# power.net
KiCad netlist of a schematic drawn in Altium Designer
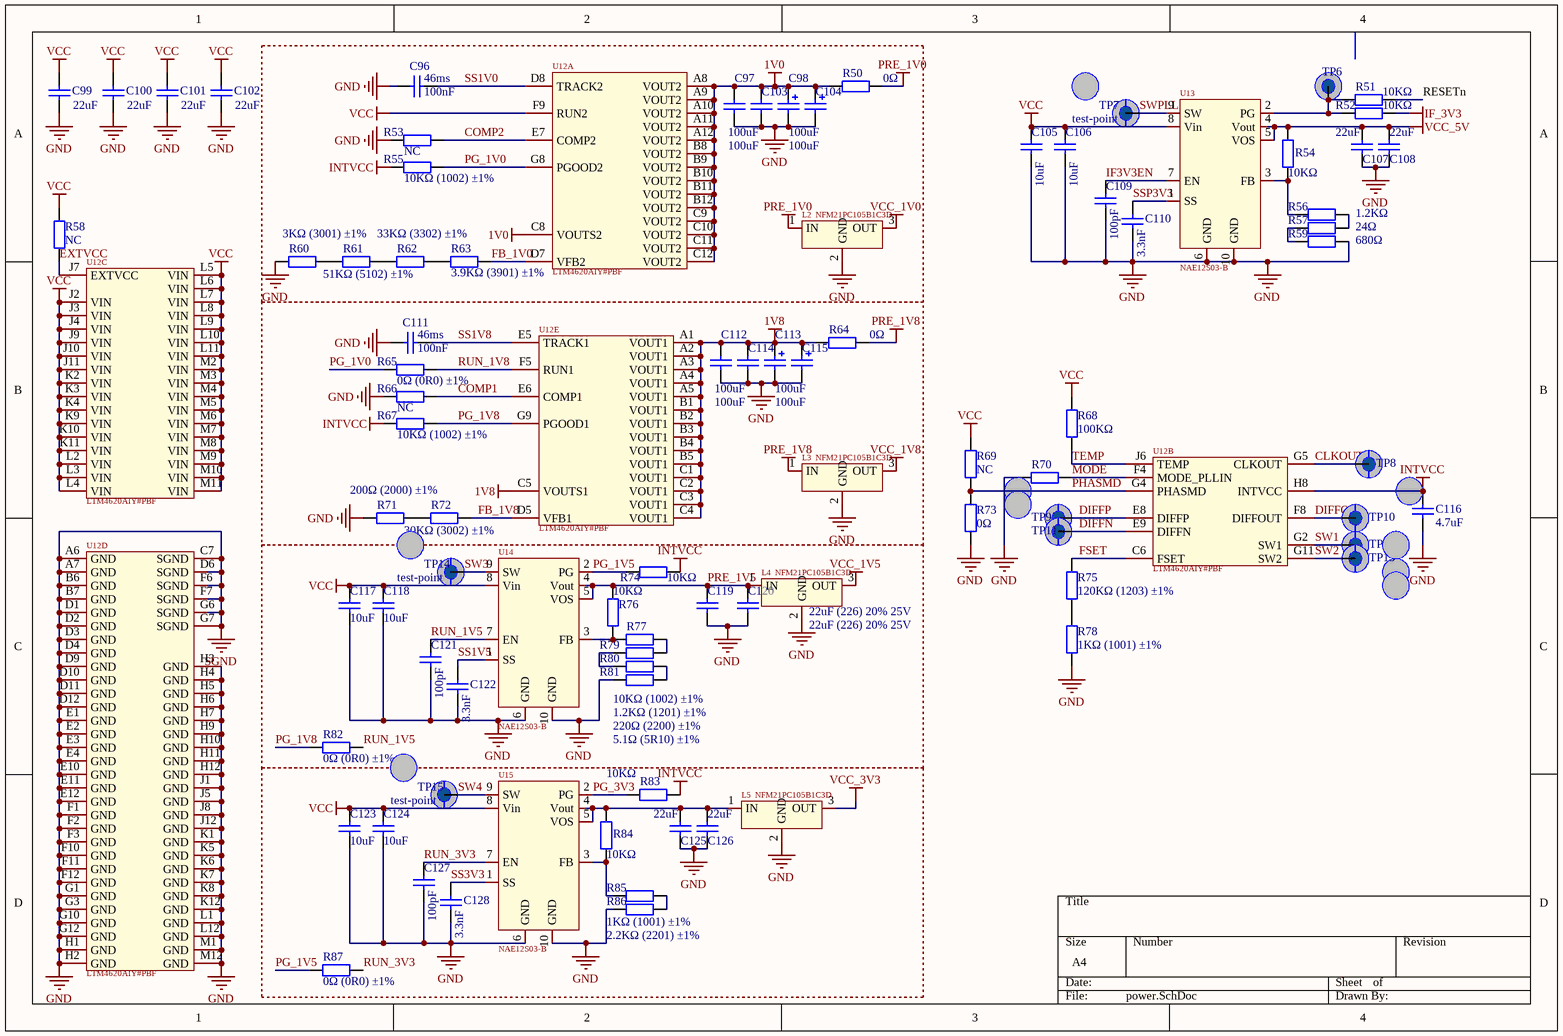
[diagram p0: power.SchDoc]

(export (version "E")
  (design (tool "Eeschema 10.0.6"))
  (components
    (comp (ref "C96")
      (value "100nF")
      (footprint "0805_C")
      (description "贴片电容")
      (libsource (lib "Miscellaneous Devices LC") (part "0805 100nF(104) 10% 50V"))
    )
    (comp (ref "C97")
      (value "100uF")
      (footprint "1206_C")
      (description "贴片电容")
      (libsource (lib "Miscellaneous Devices LC") (part "1206 100nF (104) 10% 50V"))
    )
    (comp (ref "C98")
      (value "100uF")
      (footprint "CASE-B_3528")
      (description "钽电容")
      (libsource (lib "Miscellaneous Devices LC") (part "3528 100uF (107) 10% 6.3V"))
    )
    (comp (ref "C99")
      (value "22uF")
      (footprint "0805_C")
      (description "贴片电容")
      (libsource (lib "Miscellaneous Devices LC") (part "0805 22uF (226) 20% 25V"))
    )
    (comp (ref "C100")
      (value "22uF")
      (footprint "0805_C")
      (description "贴片电容")
      (libsource (lib "Miscellaneous Devices LC") (part "0805 22uF (226) 20% 25V"))
    )
    (comp (ref "C101")
      (value "22uF")
      (footprint "0805_C")
      (description "贴片电容")
      (libsource (lib "Miscellaneous Devices LC") (part "0805 22uF (226) 20% 25V"))
    )
    (comp (ref "C102")
      (value "22uF")
      (footprint "0805_C")
      (description "贴片电容")
      (libsource (lib "Miscellaneous Devices LC") (part "0805 22uF (226) 20% 25V"))
    )
    (comp (ref "C103")
      (value "100uF")
      (footprint "1206_C")
      (description "贴片电容")
      (libsource (lib "Miscellaneous Devices LC") (part "1206 100nF (104) 10% 50V"))
    )
    (comp (ref "C104")
      (value "100uF")
      (footprint "CASE-B_3528")
      (description "钽电容")
      (libsource (lib "Miscellaneous Devices LC") (part "3528 100uF (107) 10% 6.3V"))
    )
    (comp (ref "C105")
      (value "10uF")
      (footprint "0805_C")
      (description "贴片电容")
      (libsource (lib "Miscellaneous Devices LC") (part "0805 10uF (106) 10% 25V"))
    )
    (comp (ref "C106")
      (value "10uF")
      (footprint "0805_C")
      (description "贴片电容")
      (libsource (lib "Miscellaneous Devices LC") (part "0805 10uF (106) 10% 25V"))
    )
    (comp (ref "C107")
      (value "22uF")
      (footprint "0805_C")
      (description "贴片电容")
      (libsource (lib "Miscellaneous Devices LC") (part "0805 22uF (226) 20% 25V"))
    )
    (comp (ref "C108")
      (value "22uF")
      (footprint "0805_C")
      (description "贴片电容")
      (libsource (lib "Miscellaneous Devices LC") (part "0805 22uF (226) 20% 25V"))
    )
    (comp (ref "C109")
      (value "100pF")
      (footprint "0805_C")
      (description "贴片电容")
      (libsource (lib "Miscellaneous Devices LC") (part "0805 100pF (101) 5% 50V"))
    )
    (comp (ref "C110")
      (value "3.3nF")
      (footprint "0805_C")
      (description "贴片电容")
      (libsource (lib "Miscellaneous Devices LC") (part "0805 3.3nF (332) 10% 50V"))
    )
    (comp (ref "C111")
      (value "100nF")
      (footprint "0805_C")
      (description "贴片电容")
      (libsource (lib "Miscellaneous Devices LC") (part "0805 100nF(104) 10% 50V"))
    )
    (comp (ref "C112")
      (value "100uF")
      (footprint "1206_C")
      (description "贴片电容")
      (libsource (lib "Miscellaneous Devices LC") (part "1206 100nF (104) 10% 50V"))
    )
    (comp (ref "C113")
      (value "100uF")
      (footprint "CASE-B_3528")
      (description "钽电容")
      (libsource (lib "Miscellaneous Devices LC") (part "3528 100uF (107) 10% 6.3V"))
    )
    (comp (ref "C114")
      (value "100uF")
      (footprint "1206_C")
      (description "贴片电容")
      (libsource (lib "Miscellaneous Devices LC") (part "1206 100nF (104) 10% 50V"))
    )
    (comp (ref "C115")
      (value "100uF")
      (footprint "CASE-B_3528")
      (description "钽电容")
      (libsource (lib "Miscellaneous Devices LC") (part "3528 100uF (107) 10% 6.3V"))
    )
    (comp (ref "C116")
      (value "4.7uF")
      (footprint "0805_C")
      (description "贴片电容")
      (libsource (lib "Miscellaneous Devices LC") (part "0805 4.7uF (475) 10% 25V"))
    )
    (comp (ref "C117")
      (value "10uF")
      (footprint "0805_C")
      (description "贴片电容")
      (libsource (lib "Miscellaneous Devices LC") (part "0805 10uF (106) 10% 25V"))
    )
    (comp (ref "C118")
      (value "10uF")
      (footprint "0805_C")
      (description "贴片电容")
      (libsource (lib "Miscellaneous Devices LC") (part "0805 10uF (106) 10% 25V"))
    )
    (comp (ref "C119")
      (value "22uF (226) 20% 25V")
      (footprint "0805_C")
      (description "贴片电容")
      (libsource (lib "Miscellaneous Devices LC") (part "0805 22uF (226) 20% 25V"))
    )
    (comp (ref "C120")
      (value "22uF (226) 20% 25V")
      (footprint "0805_C")
      (description "贴片电容")
      (libsource (lib "Miscellaneous Devices LC") (part "0805 22uF (226) 20% 25V"))
    )
    (comp (ref "C121")
      (value "100pF")
      (footprint "0805_C")
      (description "贴片电容")
      (libsource (lib "Miscellaneous Devices LC") (part "0805 100pF (101) 5% 50V"))
    )
    (comp (ref "C122")
      (value "3.3nF")
      (footprint "0805_C")
      (description "贴片电容")
      (libsource (lib "Miscellaneous Devices LC") (part "0805 3.3nF (332) 10% 50V"))
    )
    (comp (ref "C123")
      (value "10uF")
      (footprint "0805_C")
      (description "贴片电容")
      (libsource (lib "Miscellaneous Devices LC") (part "0805 10uF (106) 10% 25V"))
    )
    (comp (ref "C124")
      (value "10uF")
      (footprint "0805_C")
      (description "贴片电容")
      (libsource (lib "Miscellaneous Devices LC") (part "0805 10uF (106) 10% 25V"))
    )
    (comp (ref "C125")
      (value "22uF")
      (footprint "0805_C")
      (description "贴片电容")
      (libsource (lib "Miscellaneous Devices LC") (part "0805 22uF (226) 20% 25V"))
    )
    (comp (ref "C126")
      (value "22uF")
      (footprint "0805_C")
      (description "贴片电容")
      (libsource (lib "Miscellaneous Devices LC") (part "0805 22uF (226) 20% 25V"))
    )
    (comp (ref "C127")
      (value "100pF")
      (footprint "0805_C")
      (description "贴片电容")
      (libsource (lib "Miscellaneous Devices LC") (part "0805 100pF (101) 5% 50V"))
    )
    (comp (ref "C128")
      (value "3.3nF")
      (footprint "0805_C")
      (description "贴片电容")
      (libsource (lib "Miscellaneous Devices LC") (part "0805 3.3nF (332) 10% 50V"))
    )
    (comp (ref "L2")
      (value "NFM21PC105B1C3D")
      (footprint "FILTER-SMD_3P-L2.0-W1.2-L")
      (description "穿心电容")
      (fields (field (name "MANUFACTURER") "muRata(村田)"))
      (libsource (lib "五向开关") (part "NFM21PC105B1C3D"))
    )
    (comp (ref "L3")
      (value "NFM21PC105B1C3D")
      (footprint "FILTER-SMD_3P-L2.0-W1.2-L")
      (description "穿心电容")
      (fields (field (name "MANUFACTURER") "muRata(村田)"))
      (libsource (lib "五向开关") (part "NFM21PC105B1C3D"))
    )
    (comp (ref "L4")
      (value "NFM21PC105B1C3D")
      (footprint "FILTER-SMD_3P-L2.0-W1.2-L")
      (description "穿心电容")
      (fields (field (name "MANUFACTURER") "muRata(村田)"))
      (libsource (lib "五向开关") (part "NFM21PC105B1C3D"))
    )
    (comp (ref "L5")
      (value "NFM21PC105B1C3D")
      (footprint "FILTER-SMD_3P-L2.0-W1.2-L")
      (description "穿心电容")
      (fields (field (name "MANUFACTURER") "muRata(村田)"))
      (libsource (lib "五向开关") (part "NFM21PC105B1C3D"))
    )
    (comp (ref "R50")
      (value "0Ω")
      (footprint "0402_R")
      (description "贴片电阻")
      (libsource (lib "") (part "0805 0Ω (0R0) 1%_1"))
    )
    (comp (ref "R51")
      (value "10KΩ")
      (footprint "0805_R")
      (description "贴片电阻")
      (libsource (lib "Miscellaneous Devices LC") (part "0805 10KΩ (1002) 1%"))
    )
    (comp (ref "R52")
      (value "10KΩ")
      (footprint "0805_R")
      (description "贴片电阻")
      (libsource (lib "Miscellaneous Devices LC") (part "0805 10KΩ (1002) 1%"))
    )
    (comp (ref "R53")
      (value "NC")
      (footprint "0805_R")
      (description "贴片电阻")
      (libsource (lib "Miscellaneous Devices LC") (part "0805 33KΩ (3302) 1%"))
    )
    (comp (ref "R54")
      (value "10KΩ")
      (footprint "0805_R")
      (description "贴片电阻")
      (libsource (lib "") (part "0805 10KΩ (1002) 1%_1"))
    )
    (comp (ref "R55")
      (value "10KΩ (1002) ±1%")
      (footprint "0805_R")
      (description "贴片电阻")
      (libsource (lib "Miscellaneous Devices LC") (part "0805 10KΩ (1002) 1%"))
    )
    (comp (ref "R56")
      (value "1.2KΩ")
      (footprint "0805_R")
      (description "贴片电阻")
      (libsource (lib "Miscellaneous Devices LC") (part "0805 2.2KΩ (2201) 1%"))
    )
    (comp (ref "R57")
      (value "24Ω")
      (footprint "0805_R")
      (description "贴片电阻")
      (libsource (lib "") (part "0805 1KΩ (1001) 1%_1"))
    )
    (comp (ref "R58")
      (value "NC")
      (footprint "0805_R")
      (description "贴片电阻")
      (libsource (lib "") (part "0805 3KΩ (3001) 1%_1"))
    )
    (comp (ref "R59")
      (value "680Ω")
      (footprint "0805_R")
      (description "贴片电阻")
      (libsource (lib "") (part "0805 1KΩ (1001) 1%_1"))
    )
    (comp (ref "R60")
      (value "3KΩ (3001) ±1%")
      (footprint "0805_R")
      (description "贴片电阻")
      (libsource (lib "Miscellaneous Devices LC") (part "0805 3KΩ (3001) 1%"))
    )
    (comp (ref "R61")
      (value "51KΩ (5102) ±1%")
      (footprint "0805_R")
      (description "贴片电阻")
      (libsource (lib "Miscellaneous Devices LC") (part "0805 51KΩ (5102) 1%"))
    )
    (comp (ref "R62")
      (value "33KΩ (3302) ±1%")
      (footprint "0805_R")
      (description "贴片电阻")
      (libsource (lib "Miscellaneous Devices LC") (part "0805 33KΩ (3302) 1%"))
    )
    (comp (ref "R63")
      (value "3.9KΩ (3901) ±1%")
      (footprint "0805_R")
      (description "贴片电阻")
      (libsource (lib "Miscellaneous Devices LC") (part "0805 3.9KΩ (3901) 1%"))
    )
    (comp (ref "R64")
      (value "0Ω")
      (footprint "0402_R")
      (description "贴片电阻")
      (libsource (lib "") (part "0805 0Ω (0R0) 1%_1"))
    )
    (comp (ref "R65")
      (value "0Ω (0R0) ±1%")
      (footprint "0805_R")
      (description "贴片电阻")
      (libsource (lib "Miscellaneous Devices LC") (part "0805 0Ω (0R0) 1%"))
    )
    (comp (ref "R66")
      (value "NC")
      (footprint "0805_R")
      (description "贴片电阻")
      (libsource (lib "Miscellaneous Devices LC") (part "0805 33KΩ (3302) 1%"))
    )
    (comp (ref "R67")
      (value "10KΩ (1002) ±1%")
      (footprint "0805_R")
      (description "贴片电阻")
      (libsource (lib "Miscellaneous Devices LC") (part "0805 10KΩ (1002) 1%"))
    )
    (comp (ref "R68")
      (value "100KΩ")
      (footprint "0805_R")
      (description "贴片电阻")
      (libsource (lib "Miscellaneous Devices LC") (part "0805 100KΩ (1003) 1%"))
    )
    (comp (ref "R69")
      (value "NC")
      (footprint "0805_R")
      (description "贴片电阻")
      (libsource (lib "") (part "0805 0Ω (0R0) 1%_2"))
    )
    (comp (ref "R70")
      (value "0Ω")
      (footprint "0805_R")
      (description "贴片电阻")
      (libsource (lib "Miscellaneous Devices LC") (part "0805 0Ω (0R0) 1%"))
    )
    (comp (ref "R71")
      (value "200Ω (2000) ±1%")
      (footprint "0805_R")
      (description "贴片电阻")
      (libsource (lib "Miscellaneous Devices LC") (part "0805 200Ω (2000) 1%"))
    )
    (comp (ref "R72")
      (value "30KΩ (3002) ±1%")
      (footprint "0805_R")
      (description "贴片电阻")
      (libsource (lib "Miscellaneous Devices LC") (part "0805 33KΩ (3302) 1%"))
    )
    (comp (ref "R73")
      (value "0Ω")
      (footprint "0805_R")
      (description "贴片电阻")
      (libsource (lib "") (part "0805 0Ω (0R0) 1%_2"))
    )
    (comp (ref "R74")
      (value "10KΩ")
      (footprint "0805_R")
      (description "贴片电阻")
      (libsource (lib "") (part "0805 10KΩ (1002) 1%_2"))
    )
    (comp (ref "R75")
      (value "120KΩ (1203) ±1%")
      (footprint "0805_R")
      (description "贴片电阻")
      (libsource (lib "Miscellaneous Devices LC") (part "0402 120KΩ (1203) 1%"))
    )
    (comp (ref "R76")
      (value "10KΩ")
      (footprint "0805_R")
      (description "贴片电阻")
      (libsource (lib "") (part "0805 10KΩ (1002) 1%_1"))
    )
    (comp (ref "R77")
      (value "10KΩ (1002) ±1%")
      (footprint "0805_R")
      (description "贴片电阻")
      (libsource (lib "") (part "0805 10KΩ (1002) 1%_2"))
    )
    (comp (ref "R78")
      (value "1KΩ (1001) ±1%")
      (footprint "0805_R")
      (description "贴片电阻")
      (libsource (lib "Miscellaneous Devices LC") (part "0402 1KΩ (1001) 1%"))
    )
    (comp (ref "R79")
      (value "1.2KΩ (1201) ±1%")
      (footprint "0805_R")
      (description "贴片电阻")
      (libsource (lib "Miscellaneous Devices LC") (part "0805 1.2KΩ (1201) 1%"))
    )
    (comp (ref "R80")
      (value "220Ω (2200) ±1%")
      (footprint "0805_R")
      (description "贴片电阻")
      (libsource (lib "Miscellaneous Devices LC") (part "0805 220Ω (2200) 1%"))
    )
    (comp (ref "R81")
      (value "5.1Ω (5R10) ±1%")
      (footprint "0805_R")
      (description "贴片电阻")
      (libsource (lib "Miscellaneous Devices LC") (part "0805 5.1Ω (5R10) 1%"))
    )
    (comp (ref "R82")
      (value "0Ω (0R0) ±1%")
      (footprint "0805_R")
      (description "贴片电阻")
      (libsource (lib "Miscellaneous Devices LC") (part "0805 0Ω (0R0) 1%"))
    )
    (comp (ref "R83")
      (value "10KΩ")
      (footprint "0805_R")
      (description "贴片电阻")
      (libsource (lib "") (part "0805 10KΩ (1002) 1%_2"))
    )
    (comp (ref "R84")
      (value "10KΩ")
      (footprint "0805_R")
      (description "贴片电阻")
      (libsource (lib "") (part "0805 10KΩ (1002) 1%_1"))
    )
    (comp (ref "R85")
      (value "2.2KΩ (2201) ±1%")
      (footprint "0805_R")
      (description "贴片电阻")
      (libsource (lib "Miscellaneous Devices LC") (part "0805 2.2KΩ (2201) 1%"))
    )
    (comp (ref "R86")
      (value "1KΩ (1001) ±1%")
      (footprint "0805_R")
      (description "贴片电阻")
      (libsource (lib "Miscellaneous Devices LC") (part "0805 1KΩ (1001) 1%"))
    )
    (comp (ref "R87")
      (value "0Ω (0R0) ±1%")
      (footprint "0805_R")
      (description "贴片电阻")
      (libsource (lib "Miscellaneous Devices LC") (part "0805 0Ω (0R0) 1%"))
    )
    (comp (ref "TP6")
      (value "test-point")
      (footprint "POINT")
      (description "测试点")
      (libsource (lib "") (part "test-point_2"))
    )
    (comp (ref "TP7")
      (value "test-point")
      (footprint "POINT")
      (description "测试点")
      (libsource (lib "五向开关") (part "test-point"))
    )
    (comp (ref "TP8")
      (value "test-point")
      (footprint "POINT")
      (description "测试点")
      (libsource (lib "") (part "test-point_1"))
    )
    (comp (ref "TP9")
      (value "test-point")
      (footprint "POINT")
      (description "测试点")
      (libsource (lib "五向开关") (part "test-point"))
    )
    (comp (ref "TP10")
      (value "test-point")
      (footprint "POINT")
      (description "测试点")
      (libsource (lib "") (part "test-point_1"))
    )
    (comp (ref "TP11")
      (value "test-point")
      (footprint "POINT")
      (description "测试点")
      (libsource (lib "五向开关") (part "test-point"))
    )
    (comp (ref "TP12")
      (value "test-point")
      (footprint "POINT")
      (description "测试点")
      (libsource (lib "") (part "test-point_1"))
    )
    (comp (ref "TP13")
      (value "test-point")
      (footprint "POINT")
      (description "测试点")
      (libsource (lib "") (part "test-point_1"))
    )
    (comp (ref "TP14")
      (value "test-point")
      (footprint "POINT")
      (description "测试点")
      (libsource (lib "五向开关") (part "test-point"))
    )
    (comp (ref "TP15")
      (value "test-point")
      (footprint "POINT")
      (description "测试点")
      (libsource (lib "五向开关") (part "test-point"))
    )
    (comp (ref "U12")
      (value "LTM4620AIY#PBF")
      (footprint "BGA-144_L15.0-W15.0-R12-C12-P1.27-BL")
      (description "ADI电源")
      (fields (field (name "MANUFACTURER") "ADI(亚德诺)"))
      (libsource (lib "五向开关") (part "LTM4620AIY#PBF"))
    )
    (comp (ref "U13")
      (value "NAE12S03-B")
      (footprint "PWRM-SMD_HUAWEI_NAE12S03")
      (description "华为电源模块")
      (fields (field (name "MANUFACTURER") "HUAWEI(华为)"))
      (libsource (lib "五向开关") (part "NAE12S03-B"))
    )
    (comp (ref "U14")
      (value "NAE12S03-B")
      (footprint "PWRM-SMD_HUAWEI_NAE12S03")
      (description "华为电源模块")
      (fields (field (name "MANUFACTURER") "HUAWEI(华为)"))
      (libsource (lib "五向开关") (part "NAE12S03-B"))
    )
    (comp (ref "U15")
      (value "NAE12S03-B")
      (footprint "PWRM-SMD_HUAWEI_NAE12S03")
      (description "华为电源模块")
      (fields (field (name "MANUFACTURER") "HUAWEI(华为)"))
      (libsource (lib "五向开关") (part "NAE12S03-B"))
    )
  )
  (nets
    (net (code "1") (name "/CLKOUT") (class "Default")
      (node (ref "TP8") (pin "1") (pinfunction "point_1") (pintype "passive"))
      (node (ref "U12") (pin "G5") (pinfunction "CLKOUT_G5") (pintype "passive"))
    )
    (net (code "2") (name "/COMP1") (class "Default")
      (node (ref "R66") (pin "2") (pinfunction "2_2") (pintype "passive"))
      (node (ref "U12") (pin "E6") (pinfunction "COMP1_E6") (pintype "passive"))
    )
    (net (code "3") (name "/COMP2") (class "Default")
      (node (ref "R53") (pin "2") (pinfunction "2_2") (pintype "passive"))
      (node (ref "U12") (pin "E7") (pinfunction "COMP2_E7") (pintype "passive"))
    )
    (net (code "4") (name "/DIFFN") (class "Default")
      (node (ref "TP11") (pin "1") (pinfunction "point_1") (pintype "passive"))
      (node (ref "U12") (pin "E9") (pinfunction "DIFFN_E9") (pintype "passive"))
    )
    (net (code "5") (name "/DIFFO") (class "Default")
      (node (ref "TP10") (pin "1") (pinfunction "point_1") (pintype "passive"))
      (node (ref "U12") (pin "F8") (pinfunction "DIFFOUT_F8") (pintype "passive"))
    )
    (net (code "6") (name "/DIFFP") (class "Default")
      (node (ref "TP9") (pin "1") (pinfunction "point_1") (pintype "passive"))
      (node (ref "U12") (pin "E8") (pinfunction "DIFFP_E8") (pintype "passive"))
    )
    (net (code "7") (name "/EXTVCC") (class "Default")
      (node (ref "R58") (pin "2") (pinfunction "2_2") (pintype "passive"))
      (node (ref "U12") (pin "J7") (pinfunction "EXTVCC_J7") (pintype "passive"))
    )
    (net (code "8") (name "/FB_1V0") (class "Default")
      (node (ref "R63") (pin "2") (pinfunction "2_2") (pintype "passive"))
      (node (ref "U12") (pin "D7") (pinfunction "VFB2_D7") (pintype "passive"))
    )
    (net (code "9") (name "/FB_1V8") (class "Default")
      (node (ref "R72") (pin "2") (pinfunction "2_2") (pintype "passive"))
      (node (ref "U12") (pin "D5") (pinfunction "VFB1_D5") (pintype "passive"))
    )
    (net (code "10") (name "/FSET") (class "Default")
      (node (ref "R75") (pin "2") (pinfunction "2_2") (pintype "passive"))
      (node (ref "U12") (pin "C6") (pinfunction "FSET_C6") (pintype "passive"))
    )
    (net (code "11") (name "/IF3V3EN") (class "Default")
      (node (ref "C109") (pin "2") (pinfunction "2_2") (pintype "passive"))
      (node (ref "U13") (pin "7") (pinfunction "EN_7") (pintype "passive"))
    )
    (net (code "12") (name "/MODE") (class "Default")
      (node (ref "R70") (pin "1") (pinfunction "1_1") (pintype "passive"))
      (node (ref "U12") (pin "F4") (pinfunction "MODE_PLLIN_F4") (pintype "passive"))
    )
    (net (code "13") (name "/PG_1V0") (class "Default")
      (node (ref "R55") (pin "1") (pinfunction "1_1") (pintype "passive"))
      (node (ref "R65") (pin "2") (pinfunction "2_2") (pintype "passive"))
      (node (ref "U12") (pin "G8") (pinfunction "PGOOD2_G8") (pintype "passive"))
    )
    (net (code "14") (name "/PG_1V5") (class "Default")
      (node (ref "R74") (pin "1") (pinfunction "1_1") (pintype "passive"))
      (node (ref "R87") (pin "2") (pinfunction "2_2") (pintype "passive"))
      (node (ref "U14") (pin "2") (pinfunction "PG_2") (pintype "passive"))
    )
    (net (code "15") (name "/PG_1V8") (class "Default")
      (node (ref "R67") (pin "1") (pinfunction "1_1") (pintype "passive"))
      (node (ref "R82") (pin "2") (pinfunction "2_2") (pintype "passive"))
      (node (ref "U12") (pin "G9") (pinfunction "PGOOD1_G9") (pintype "passive"))
    )
    (net (code "16") (name "/PG_3V3") (class "Default")
      (node (ref "R83") (pin "1") (pinfunction "1_1") (pintype "passive"))
      (node (ref "U15") (pin "2") (pinfunction "PG_2") (pintype "passive"))
    )
    (net (code "17") (name "/PHASMD") (class "Default")
      (node (ref "R69") (pin "1") (pinfunction "1_1") (pintype "passive"))
      (node (ref "R73") (pin "2") (pinfunction "2_2") (pintype "passive"))
      (node (ref "U12") (pin "G4") (pinfunction "PHASMD_G4") (pintype "passive"))
    )
    (net (code "18") (name "/PRE_1V5") (class "Default")
      (node (ref "C119") (pin "2") (pinfunction "2_2") (pintype "passive"))
      (node (ref "C120") (pin "2") (pinfunction "2_2") (pintype "passive"))
      (node (ref "L4") (pin "1") (pinfunction "IN_1") (pintype "passive"))
      (node (ref "R76") (pin "2") (pinfunction "2_2") (pintype "passive"))
      (node (ref "U14") (pin "4") (pinfunction "Vout_4") (pintype "passive"))
      (node (ref "U14") (pin "5") (pinfunction "VOS_5") (pintype "passive"))
    )
    (net (code "19") (name "/RESETn") (class "Default")
      (node (ref "R51") (pin "1") (pinfunction "1_1") (pintype "passive"))
    )
    (net (code "20") (name "/RUN_1V5") (class "Default")
      (node (ref "C121") (pin "2") (pinfunction "2_2") (pintype "passive"))
      (node (ref "R82") (pin "1") (pinfunction "1_1") (pintype "passive"))
      (node (ref "U14") (pin "7") (pinfunction "EN_7") (pintype "passive"))
    )
    (net (code "21") (name "/RUN_1V8") (class "Default")
      (node (ref "R65") (pin "1") (pinfunction "1_1") (pintype "passive"))
      (node (ref "U12") (pin "F5") (pinfunction "RUN1_F5") (pintype "passive"))
    )
    (net (code "22") (name "/RUN_3V3") (class "Default")
      (node (ref "C127") (pin "2") (pinfunction "2_2") (pintype "passive"))
      (node (ref "R87") (pin "1") (pinfunction "1_1") (pintype "passive"))
      (node (ref "U15") (pin "7") (pinfunction "EN_7") (pintype "passive"))
    )
    (net (code "23") (name "/SS1V0") (class "Default")
      (node (ref "C96") (pin "1") (pinfunction "1_1") (pintype "passive"))
      (node (ref "U12") (pin "D8") (pinfunction "TRACK2_D8") (pintype "passive"))
    )
    (net (code "24") (name "/SS1V5") (class "Default")
      (node (ref "C122") (pin "2") (pinfunction "2_2") (pintype "passive"))
      (node (ref "U14") (pin "1") (pinfunction "SS_1") (pintype "passive"))
    )
    (net (code "25") (name "/SS1V8") (class "Default")
      (node (ref "C111") (pin "1") (pinfunction "1_1") (pintype "passive"))
      (node (ref "U12") (pin "E5") (pinfunction "TRACK1_E5") (pintype "passive"))
    )
    (net (code "26") (name "/SS3V3") (class "Default")
      (node (ref "C128") (pin "2") (pinfunction "2_2") (pintype "passive"))
      (node (ref "U15") (pin "1") (pinfunction "SS_1") (pintype "passive"))
    )
    (net (code "27") (name "/SSP3V3") (class "Default")
      (node (ref "C110") (pin "2") (pinfunction "2_2") (pintype "passive"))
      (node (ref "U13") (pin "1") (pinfunction "SS_1") (pintype "passive"))
    )
    (net (code "28") (name "/SW1") (class "Default")
      (node (ref "TP12") (pin "1") (pinfunction "point_1") (pintype "passive"))
      (node (ref "U12") (pin "G2") (pinfunction "SW1_G2") (pintype "passive"))
    )
    (net (code "29") (name "/SW2") (class "Default")
      (node (ref "TP13") (pin "1") (pinfunction "point_1") (pintype "passive"))
      (node (ref "U12") (pin "G11") (pinfunction "SW2_G11") (pintype "passive"))
    )
    (net (code "30") (name "/SW3") (class "Default")
      (node (ref "TP14") (pin "1") (pinfunction "point_1") (pintype "passive"))
      (node (ref "U14") (pin "9") (pinfunction "SW_9") (pintype "passive"))
    )
    (net (code "31") (name "/SW4") (class "Default")
      (node (ref "TP15") (pin "1") (pinfunction "point_1") (pintype "passive"))
      (node (ref "U15") (pin "9") (pinfunction "SW_9") (pintype "passive"))
    )
    (net (code "32") (name "/SWPLL") (class "Default")
      (node (ref "TP7") (pin "1") (pinfunction "point_1") (pintype "passive"))
      (node (ref "U13") (pin "9") (pinfunction "SW_9") (pintype "passive"))
    )
    (net (code "33") (name "/TEMP") (class "Default")
      (node (ref "R68") (pin "1") (pinfunction "1_1") (pintype "passive"))
      (node (ref "U12") (pin "J6") (pinfunction "TEMP_J6") (pintype "passive"))
    )
    (net (code "34") (name "1V0") (class "Default")
      (node (ref "C103") (pin "2") (pinfunction "2_2") (pintype "passive"))
      (node (ref "C104") (pin "1") (pinfunction "1_1") (pintype "passive"))
      (node (ref "C97") (pin "2") (pinfunction "2_2") (pintype "passive"))
      (node (ref "C98") (pin "1") (pinfunction "1_1") (pintype "passive"))
      (node (ref "R50") (pin "1") (pinfunction "1_1") (pintype "passive"))
      (node (ref "U12") (pin "A10") (pinfunction "VOUT2_A10") (pintype "passive"))
      (node (ref "U12") (pin "A11") (pinfunction "VOUT2_A11") (pintype "passive"))
      (node (ref "U12") (pin "A12") (pinfunction "VOUT2_A12") (pintype "passive"))
      (node (ref "U12") (pin "A8") (pinfunction "VOUT2_A8") (pintype "passive"))
      (node (ref "U12") (pin "A9") (pinfunction "VOUT2_A9") (pintype "passive"))
      (node (ref "U12") (pin "B10") (pinfunction "VOUT2_B10") (pintype "passive"))
      (node (ref "U12") (pin "B11") (pinfunction "VOUT2_B11") (pintype "passive"))
      (node (ref "U12") (pin "B12") (pinfunction "VOUT2_B12") (pintype "passive"))
      (node (ref "U12") (pin "B8") (pinfunction "VOUT2_B8") (pintype "passive"))
      (node (ref "U12") (pin "B9") (pinfunction "VOUT2_B9") (pintype "passive"))
      (node (ref "U12") (pin "C10") (pinfunction "VOUT2_C10") (pintype "passive"))
      (node (ref "U12") (pin "C11") (pinfunction "VOUT2_C11") (pintype "passive"))
      (node (ref "U12") (pin "C12") (pinfunction "VOUT2_C12") (pintype "passive"))
      (node (ref "U12") (pin "C8") (pinfunction "VOUTS2_C8") (pintype "passive"))
      (node (ref "U12") (pin "C9") (pinfunction "VOUT2_C9") (pintype "passive"))
    )
    (net (code "35") (name "1V8") (class "Default")
      (node (ref "C112") (pin "2") (pinfunction "2_2") (pintype "passive"))
      (node (ref "C113") (pin "1") (pinfunction "1_1") (pintype "passive"))
      (node (ref "C114") (pin "2") (pinfunction "2_2") (pintype "passive"))
      (node (ref "C115") (pin "1") (pinfunction "1_1") (pintype "passive"))
      (node (ref "R64") (pin "1") (pinfunction "1_1") (pintype "passive"))
      (node (ref "U12") (pin "A1") (pinfunction "VOUT1_A1") (pintype "passive"))
      (node (ref "U12") (pin "A2") (pinfunction "VOUT1_A2") (pintype "passive"))
      (node (ref "U12") (pin "A3") (pinfunction "VOUT1_A3") (pintype "passive"))
      (node (ref "U12") (pin "A4") (pinfunction "VOUT1_A4") (pintype "passive"))
      (node (ref "U12") (pin "A5") (pinfunction "VOUT1_A5") (pintype "passive"))
      (node (ref "U12") (pin "B1") (pinfunction "VOUT1_B1") (pintype "passive"))
      (node (ref "U12") (pin "B2") (pinfunction "VOUT1_B2") (pintype "passive"))
      (node (ref "U12") (pin "B3") (pinfunction "VOUT1_B3") (pintype "passive"))
      (node (ref "U12") (pin "B4") (pinfunction "VOUT1_B4") (pintype "passive"))
      (node (ref "U12") (pin "B5") (pinfunction "VOUT1_B5") (pintype "passive"))
      (node (ref "U12") (pin "C1") (pinfunction "VOUT1_C1") (pintype "passive"))
      (node (ref "U12") (pin "C2") (pinfunction "VOUT1_C2") (pintype "passive"))
      (node (ref "U12") (pin "C3") (pinfunction "VOUT1_C3") (pintype "passive"))
      (node (ref "U12") (pin "C4") (pinfunction "VOUT1_C4") (pintype "passive"))
      (node (ref "U12") (pin "C5") (pinfunction "VOUTS1_C5") (pintype "passive"))
    )
    (net (code "36") (name "GND") (class "Default")
      (node (ref "C100") (pin "1") (pinfunction "1_1") (pintype "passive"))
      (node (ref "C101") (pin "1") (pinfunction "1_1") (pintype "passive"))
      (node (ref "C102") (pin "1") (pinfunction "1_1") (pintype "passive"))
      (node (ref "C103") (pin "1") (pinfunction "1_1") (pintype "passive"))
      (node (ref "C104") (pin "2") (pinfunction "2_2") (pintype "passive"))
      (node (ref "C105") (pin "1") (pinfunction "1_1") (pintype "passive"))
      (node (ref "C106") (pin "1") (pinfunction "1_1") (pintype "passive"))
      (node (ref "C107") (pin "1") (pinfunction "1_1") (pintype "passive"))
      (node (ref "C108") (pin "1") (pinfunction "1_1") (pintype "passive"))
      (node (ref "C109") (pin "1") (pinfunction "1_1") (pintype "passive"))
      (node (ref "C110") (pin "1") (pinfunction "1_1") (pintype "passive"))
      (node (ref "C111") (pin "2") (pinfunction "2_2") (pintype "passive"))
      (node (ref "C112") (pin "1") (pinfunction "1_1") (pintype "passive"))
      (node (ref "C113") (pin "2") (pinfunction "2_2") (pintype "passive"))
      (node (ref "C114") (pin "1") (pinfunction "1_1") (pintype "passive"))
      (node (ref "C115") (pin "2") (pinfunction "2_2") (pintype "passive"))
      (node (ref "C116") (pin "1") (pinfunction "1_1") (pintype "passive"))
      (node (ref "C117") (pin "1") (pinfunction "1_1") (pintype "passive"))
      (node (ref "C118") (pin "1") (pinfunction "1_1") (pintype "passive"))
      (node (ref "C119") (pin "1") (pinfunction "1_1") (pintype "passive"))
      (node (ref "C120") (pin "1") (pinfunction "1_1") (pintype "passive"))
      (node (ref "C121") (pin "1") (pinfunction "1_1") (pintype "passive"))
      (node (ref "C122") (pin "1") (pinfunction "1_1") (pintype "passive"))
      (node (ref "C123") (pin "1") (pinfunction "1_1") (pintype "passive"))
      (node (ref "C124") (pin "1") (pinfunction "1_1") (pintype "passive"))
      (node (ref "C125") (pin "1") (pinfunction "1_1") (pintype "passive"))
      (node (ref "C126") (pin "1") (pinfunction "1_1") (pintype "passive"))
      (node (ref "C127") (pin "1") (pinfunction "1_1") (pintype "passive"))
      (node (ref "C128") (pin "1") (pinfunction "1_1") (pintype "passive"))
      (node (ref "C96") (pin "2") (pinfunction "2_2") (pintype "passive"))
      (node (ref "C97") (pin "1") (pinfunction "1_1") (pintype "passive"))
      (node (ref "C98") (pin "2") (pinfunction "2_2") (pintype "passive"))
      (node (ref "C99") (pin "1") (pinfunction "1_1") (pintype "passive"))
      (node (ref "L2") (pin "2") (pinfunction "GND_2") (pintype "passive"))
      (node (ref "L3") (pin "2") (pinfunction "GND_2") (pintype "passive"))
      (node (ref "L4") (pin "2") (pinfunction "GND_2") (pintype "passive"))
      (node (ref "L5") (pin "2") (pinfunction "GND_2") (pintype "passive"))
      (node (ref "R53") (pin "1") (pinfunction "1_1") (pintype "passive"))
      (node (ref "R59") (pin "2") (pinfunction "2_2") (pintype "passive"))
      (node (ref "R60") (pin "2") (pinfunction "2_2") (pintype "passive"))
      (node (ref "R66") (pin "1") (pinfunction "1_1") (pintype "passive"))
      (node (ref "R70") (pin "2") (pinfunction "2_2") (pintype "passive"))
      (node (ref "R71") (pin "1") (pinfunction "1_1") (pintype "passive"))
      (node (ref "R73") (pin "1") (pinfunction "1_1") (pintype "passive"))
      (node (ref "R78") (pin "1") (pinfunction "1_1") (pintype "passive"))
      (node (ref "R81") (pin "2") (pinfunction "2_2") (pintype "passive"))
      (node (ref "R86") (pin "2") (pinfunction "2_2") (pintype "passive"))
      (node (ref "U12") (pin "A6") (pinfunction "GND_A6") (pintype "passive"))
      (node (ref "U12") (pin "A7") (pinfunction "GND_A7") (pintype "passive"))
      (node (ref "U12") (pin "B6") (pinfunction "GND_B6") (pintype "passive"))
      (node (ref "U12") (pin "B7") (pinfunction "GND_B7") (pintype "passive"))
      (node (ref "U12") (pin "C7") (pinfunction "SGND_C7") (pintype "passive"))
      (node (ref "U12") (pin "D1") (pinfunction "GND_D1") (pintype "passive"))
      (node (ref "U12") (pin "D10") (pinfunction "GND_D10") (pintype "passive"))
      (node (ref "U12") (pin "D11") (pinfunction "GND_D11") (pintype "passive"))
      (node (ref "U12") (pin "D12") (pinfunction "GND_D12") (pintype "passive"))
      (node (ref "U12") (pin "D2") (pinfunction "GND_D2") (pintype "passive"))
      (node (ref "U12") (pin "D3") (pinfunction "GND_D3") (pintype "passive"))
      (node (ref "U12") (pin "D4") (pinfunction "GND_D4") (pintype "passive"))
      (node (ref "U12") (pin "D6") (pinfunction "SGND_D6") (pintype "passive"))
      (node (ref "U12") (pin "D9") (pinfunction "GND_D9") (pintype "passive"))
      (node (ref "U12") (pin "E1") (pinfunction "GND_E1") (pintype "passive"))
      (node (ref "U12") (pin "E10") (pinfunction "GND_E10") (pintype "passive"))
      (node (ref "U12") (pin "E11") (pinfunction "GND_E11") (pintype "passive"))
      (node (ref "U12") (pin "E12") (pinfunction "GND_E12") (pintype "passive"))
      (node (ref "U12") (pin "E2") (pinfunction "GND_E2") (pintype "passive"))
      (node (ref "U12") (pin "E3") (pinfunction "GND_E3") (pintype "passive"))
      (node (ref "U12") (pin "E4") (pinfunction "GND_E4") (pintype "passive"))
      (node (ref "U12") (pin "F1") (pinfunction "GND_F1") (pintype "passive"))
      (node (ref "U12") (pin "F10") (pinfunction "GND_F10") (pintype "passive"))
      (node (ref "U12") (pin "F11") (pinfunction "GND_F11") (pintype "passive"))
      (node (ref "U12") (pin "F12") (pinfunction "GND_F12") (pintype "passive"))
      (node (ref "U12") (pin "F2") (pinfunction "GND_F2") (pintype "passive"))
      (node (ref "U12") (pin "F3") (pinfunction "GND_F3") (pintype "passive"))
      (node (ref "U12") (pin "F6") (pinfunction "SGND_F6") (pintype "passive"))
      (node (ref "U12") (pin "F7") (pinfunction "SGND_F7") (pintype "passive"))
      (node (ref "U12") (pin "G1") (pinfunction "GND_G1") (pintype "passive"))
      (node (ref "U12") (pin "G10") (pinfunction "GND_G10") (pintype "passive"))
      (node (ref "U12") (pin "G12") (pinfunction "GND_G12") (pintype "passive"))
      (node (ref "U12") (pin "G3") (pinfunction "GND_G3") (pintype "passive"))
      (node (ref "U12") (pin "G6") (pinfunction "SGND_G6") (pintype "passive"))
      (node (ref "U12") (pin "G7") (pinfunction "SGND_G7") (pintype "passive"))
      (node (ref "U12") (pin "H1") (pinfunction "GND_H1") (pintype "passive"))
      (node (ref "U12") (pin "H10") (pinfunction "GND_H10") (pintype "passive"))
      (node (ref "U12") (pin "H11") (pinfunction "GND_H11") (pintype "passive"))
      (node (ref "U12") (pin "H12") (pinfunction "GND_H12") (pintype "passive"))
      (node (ref "U12") (pin "H2") (pinfunction "GND_H2") (pintype "passive"))
      (node (ref "U12") (pin "H3") (pinfunction "GND_H3") (pintype "passive"))
      (node (ref "U12") (pin "H4") (pinfunction "GND_H4") (pintype "passive"))
      (node (ref "U12") (pin "H5") (pinfunction "GND_H5") (pintype "passive"))
      (node (ref "U12") (pin "H6") (pinfunction "GND_H6") (pintype "passive"))
      (node (ref "U12") (pin "H7") (pinfunction "GND_H7") (pintype "passive"))
      (node (ref "U12") (pin "H9") (pinfunction "GND_H9") (pintype "passive"))
      (node (ref "U12") (pin "J1") (pinfunction "GND_J1") (pintype "passive"))
      (node (ref "U12") (pin "J12") (pinfunction "GND_J12") (pintype "passive"))
      (node (ref "U12") (pin "J5") (pinfunction "GND_J5") (pintype "passive"))
      (node (ref "U12") (pin "J8") (pinfunction "GND_J8") (pintype "passive"))
      (node (ref "U12") (pin "K1") (pinfunction "GND_K1") (pintype "passive"))
      (node (ref "U12") (pin "K12") (pinfunction "GND_K12") (pintype "passive"))
      (node (ref "U12") (pin "K5") (pinfunction "GND_K5") (pintype "passive"))
      (node (ref "U12") (pin "K6") (pinfunction "GND_K6") (pintype "passive"))
      (node (ref "U12") (pin "K7") (pinfunction "GND_K7") (pintype "passive"))
      (node (ref "U12") (pin "K8") (pinfunction "GND_K8") (pintype "passive"))
      (node (ref "U12") (pin "L1") (pinfunction "GND_L1") (pintype "passive"))
      (node (ref "U12") (pin "L12") (pinfunction "GND_L12") (pintype "passive"))
      (node (ref "U12") (pin "M1") (pinfunction "GND_M1") (pintype "passive"))
      (node (ref "U12") (pin "M12") (pinfunction "GND_M12") (pintype "passive"))
      (node (ref "U13") (pin "10") (pinfunction "GND_10") (pintype "passive"))
      (node (ref "U13") (pin "6") (pinfunction "GND_6") (pintype "passive"))
      (node (ref "U14") (pin "10") (pinfunction "GND_10") (pintype "passive"))
      (node (ref "U14") (pin "6") (pinfunction "GND_6") (pintype "passive"))
      (node (ref "U15") (pin "10") (pinfunction "GND_10") (pintype "passive"))
      (node (ref "U15") (pin "6") (pinfunction "GND_6") (pintype "passive"))
    )
    (net (code "37") (name "IF_3V3") (class "Default")
      (node (ref "R52") (pin "1") (pinfunction "1_1") (pintype "passive"))
    )
    (net (code "38") (name "INTVCC") (class "Default")
      (node (ref "C116") (pin "2") (pinfunction "2_2") (pintype "passive"))
      (node (ref "R55") (pin "2") (pinfunction "2_2") (pintype "passive"))
      (node (ref "R67") (pin "2") (pinfunction "2_2") (pintype "passive"))
      (node (ref "R74") (pin "2") (pinfunction "2_2") (pintype "passive"))
      (node (ref "R83") (pin "2") (pinfunction "2_2") (pintype "passive"))
      (node (ref "U12") (pin "H8") (pinfunction "INTVCC_H8") (pintype "passive"))
    )
    (net (code "39") (name "Net-(L5-IN)") (class "Default")
      (node (ref "C125") (pin "2") (pinfunction "2_2") (pintype "passive"))
      (node (ref "C126") (pin "2") (pinfunction "2_2") (pintype "passive"))
      (node (ref "L5") (pin "1") (pinfunction "IN_1") (pintype "passive"))
      (node (ref "R84") (pin "2") (pinfunction "2_2") (pintype "passive"))
      (node (ref "U15") (pin "4") (pinfunction "Vout_4") (pintype "passive"))
      (node (ref "U15") (pin "5") (pinfunction "VOS_5") (pintype "passive"))
    )
    (net (code "40") (name "Net-(R56-Pad2)") (class "Default")
      (node (ref "R56") (pin "2") (pinfunction "2_2") (pintype "passive"))
      (node (ref "R57") (pin "2") (pinfunction "2_2") (pintype "passive"))
    )
    (net (code "41") (name "Net-(R57-Pad1)") (class "Default")
      (node (ref "R57") (pin "1") (pinfunction "1_1") (pintype "passive"))
      (node (ref "R59") (pin "1") (pinfunction "1_1") (pintype "passive"))
    )
    (net (code "42") (name "Net-(R60-Pad1)") (class "Default")
      (node (ref "R60") (pin "1") (pinfunction "1_1") (pintype "passive"))
      (node (ref "R61") (pin "1") (pinfunction "1_1") (pintype "passive"))
    )
    (net (code "43") (name "Net-(R61-Pad2)") (class "Default")
      (node (ref "R61") (pin "2") (pinfunction "2_2") (pintype "passive"))
      (node (ref "R62") (pin "1") (pinfunction "1_1") (pintype "passive"))
    )
    (net (code "44") (name "Net-(R62-Pad2)") (class "Default")
      (node (ref "R62") (pin "2") (pinfunction "2_2") (pintype "passive"))
      (node (ref "R63") (pin "1") (pinfunction "1_1") (pintype "passive"))
    )
    (net (code "45") (name "Net-(R71-Pad2)") (class "Default")
      (node (ref "R71") (pin "2") (pinfunction "2_2") (pintype "passive"))
      (node (ref "R72") (pin "1") (pinfunction "1_1") (pintype "passive"))
    )
    (net (code "46") (name "Net-(R75-Pad1)") (class "Default")
      (node (ref "R75") (pin "1") (pinfunction "1_1") (pintype "passive"))
      (node (ref "R78") (pin "2") (pinfunction "2_2") (pintype "passive"))
    )
    (net (code "47") (name "Net-(R77-Pad2)") (class "Default")
      (node (ref "R77") (pin "2") (pinfunction "2_2") (pintype "passive"))
      (node (ref "R79") (pin "1") (pinfunction "1_1") (pintype "passive"))
    )
    (net (code "48") (name "Net-(R79-Pad2)") (class "Default")
      (node (ref "R79") (pin "2") (pinfunction "2_2") (pintype "passive"))
      (node (ref "R80") (pin "2") (pinfunction "2_2") (pintype "passive"))
    )
    (net (code "49") (name "Net-(R80-Pad1)") (class "Default")
      (node (ref "R80") (pin "1") (pinfunction "1_1") (pintype "passive"))
      (node (ref "R81") (pin "1") (pinfunction "1_1") (pintype "passive"))
    )
    (net (code "50") (name "Net-(R85-Pad2)") (class "Default")
      (node (ref "R85") (pin "2") (pinfunction "2_2") (pintype "passive"))
      (node (ref "R86") (pin "1") (pinfunction "1_1") (pintype "passive"))
    )
    (net (code "51") (name "Net-(TP6-point)") (class "Default")
      (node (ref "R51") (pin "2") (pinfunction "2_2") (pintype "passive"))
      (node (ref "R52") (pin "2") (pinfunction "2_2") (pintype "passive"))
      (node (ref "TP6") (pin "1") (pinfunction "point_1") (pintype "passive"))
      (node (ref "U13") (pin "2") (pinfunction "PG_2") (pintype "passive"))
    )
    (net (code "52") (name "Net-(U13-FB)") (class "Default")
      (node (ref "R54") (pin "1") (pinfunction "1_1") (pintype "passive"))
      (node (ref "R56") (pin "1") (pinfunction "1_1") (pintype "passive"))
      (node (ref "U13") (pin "3") (pinfunction "FB_3") (pintype "passive"))
    )
    (net (code "53") (name "Net-(U14-FB)") (class "Default")
      (node (ref "R76") (pin "1") (pinfunction "1_1") (pintype "passive"))
      (node (ref "R77") (pin "1") (pinfunction "1_1") (pintype "passive"))
      (node (ref "U14") (pin "3") (pinfunction "FB_3") (pintype "passive"))
    )
    (net (code "54") (name "Net-(U15-FB)") (class "Default")
      (node (ref "R84") (pin "1") (pinfunction "1_1") (pintype "passive"))
      (node (ref "R85") (pin "1") (pinfunction "1_1") (pintype "passive"))
      (node (ref "U15") (pin "3") (pinfunction "FB_3") (pintype "passive"))
    )
    (net (code "55") (name "PRE_1V0") (class "Default")
      (node (ref "L2") (pin "1") (pinfunction "IN_1") (pintype "passive"))
      (node (ref "R50") (pin "2") (pinfunction "2_2") (pintype "passive"))
    )
    (net (code "56") (name "PRE_1V8") (class "Default")
      (node (ref "L3") (pin "1") (pinfunction "IN_1") (pintype "passive"))
      (node (ref "R64") (pin "2") (pinfunction "2_2") (pintype "passive"))
    )
    (net (code "57") (name "VCC") (class "Default")
      (node (ref "C100") (pin "2") (pinfunction "2_2") (pintype "passive"))
      (node (ref "C101") (pin "2") (pinfunction "2_2") (pintype "passive"))
      (node (ref "C102") (pin "2") (pinfunction "2_2") (pintype "passive"))
      (node (ref "C105") (pin "2") (pinfunction "2_2") (pintype "passive"))
      (node (ref "C106") (pin "2") (pinfunction "2_2") (pintype "passive"))
      (node (ref "C117") (pin "2") (pinfunction "2_2") (pintype "passive"))
      (node (ref "C118") (pin "2") (pinfunction "2_2") (pintype "passive"))
      (node (ref "C123") (pin "2") (pinfunction "2_2") (pintype "passive"))
      (node (ref "C124") (pin "2") (pinfunction "2_2") (pintype "passive"))
      (node (ref "C99") (pin "2") (pinfunction "2_2") (pintype "passive"))
      (node (ref "R58") (pin "1") (pinfunction "1_1") (pintype "passive"))
      (node (ref "R68") (pin "2") (pinfunction "2_2") (pintype "passive"))
      (node (ref "R69") (pin "2") (pinfunction "2_2") (pintype "passive"))
      (node (ref "U12") (pin "F9") (pinfunction "RUN2_F9") (pintype "passive"))
      (node (ref "U12") (pin "J10") (pinfunction "VIN_J10") (pintype "passive"))
      (node (ref "U12") (pin "J11") (pinfunction "VIN_J11") (pintype "passive"))
      (node (ref "U12") (pin "J2") (pinfunction "VIN_J2") (pintype "passive"))
      (node (ref "U12") (pin "J3") (pinfunction "VIN_J3") (pintype "passive"))
      (node (ref "U12") (pin "J4") (pinfunction "VIN_J4") (pintype "passive"))
      (node (ref "U12") (pin "J9") (pinfunction "VIN_J9") (pintype "passive"))
      (node (ref "U12") (pin "K10") (pinfunction "VIN_K10") (pintype "passive"))
      (node (ref "U12") (pin "K11") (pinfunction "VIN_K11") (pintype "passive"))
      (node (ref "U12") (pin "K2") (pinfunction "VIN_K2") (pintype "passive"))
      (node (ref "U12") (pin "K3") (pinfunction "VIN_K3") (pintype "passive"))
      (node (ref "U12") (pin "K4") (pinfunction "VIN_K4") (pintype "passive"))
      (node (ref "U12") (pin "K9") (pinfunction "VIN_K9") (pintype "passive"))
      (node (ref "U12") (pin "L10") (pinfunction "VIN_L10") (pintype "passive"))
      (node (ref "U12") (pin "L11") (pinfunction "VIN_L11") (pintype "passive"))
      (node (ref "U12") (pin "L2") (pinfunction "VIN_L2") (pintype "passive"))
      (node (ref "U12") (pin "L3") (pinfunction "VIN_L3") (pintype "passive"))
      (node (ref "U12") (pin "L4") (pinfunction "VIN_L4") (pintype "passive"))
      (node (ref "U12") (pin "L5") (pinfunction "VIN_L5") (pintype "passive"))
      (node (ref "U12") (pin "L6") (pinfunction "VIN_L6") (pintype "passive"))
      (node (ref "U12") (pin "L7") (pinfunction "VIN_L7") (pintype "passive"))
      (node (ref "U12") (pin "L8") (pinfunction "VIN_L8") (pintype "passive"))
      (node (ref "U12") (pin "L9") (pinfunction "VIN_L9") (pintype "passive"))
      (node (ref "U12") (pin "M10") (pinfunction "VIN_M10") (pintype "passive"))
      (node (ref "U12") (pin "M11") (pinfunction "VIN_M11") (pintype "passive"))
      (node (ref "U12") (pin "M2") (pinfunction "VIN_M2") (pintype "passive"))
      (node (ref "U12") (pin "M3") (pinfunction "VIN_M3") (pintype "passive"))
      (node (ref "U12") (pin "M4") (pinfunction "VIN_M4") (pintype "passive"))
      (node (ref "U12") (pin "M5") (pinfunction "VIN_M5") (pintype "passive"))
      (node (ref "U12") (pin "M6") (pinfunction "VIN_M6") (pintype "passive"))
      (node (ref "U12") (pin "M7") (pinfunction "VIN_M7") (pintype "passive"))
      (node (ref "U12") (pin "M8") (pinfunction "VIN_M8") (pintype "passive"))
      (node (ref "U12") (pin "M9") (pinfunction "VIN_M9") (pintype "passive"))
      (node (ref "U13") (pin "8") (pinfunction "Vin_8") (pintype "passive"))
      (node (ref "U14") (pin "8") (pinfunction "Vin_8") (pintype "passive"))
      (node (ref "U15") (pin "8") (pinfunction "Vin_8") (pintype "passive"))
    )
    (net (code "58") (name "VCC_1V0") (class "Default")
      (node (ref "L2") (pin "3") (pinfunction "OUT_3") (pintype "passive"))
    )
    (net (code "59") (name "VCC_1V5") (class "Default")
      (node (ref "L4") (pin "3") (pinfunction "OUT_3") (pintype "passive"))
    )
    (net (code "60") (name "VCC_1V8") (class "Default")
      (node (ref "L3") (pin "3") (pinfunction "OUT_3") (pintype "passive"))
    )
    (net (code "61") (name "VCC_3V3") (class "Default")
      (node (ref "L5") (pin "3") (pinfunction "OUT_3") (pintype "passive"))
    )
    (net (code "62") (name "VCC_5V") (class "Default")
      (node (ref "C107") (pin "2") (pinfunction "2_2") (pintype "passive"))
      (node (ref "C108") (pin "2") (pinfunction "2_2") (pintype "passive"))
      (node (ref "R54") (pin "2") (pinfunction "2_2") (pintype "passive"))
      (node (ref "U13") (pin "4") (pinfunction "Vout_4") (pintype "passive"))
      (node (ref "U13") (pin "5") (pinfunction "VOS_5") (pintype "passive"))
    )
  )
)
